# SCH_Water-Gauge_2025-03-27.net
KiCad netlist of a schematic drawn in EasyEDA
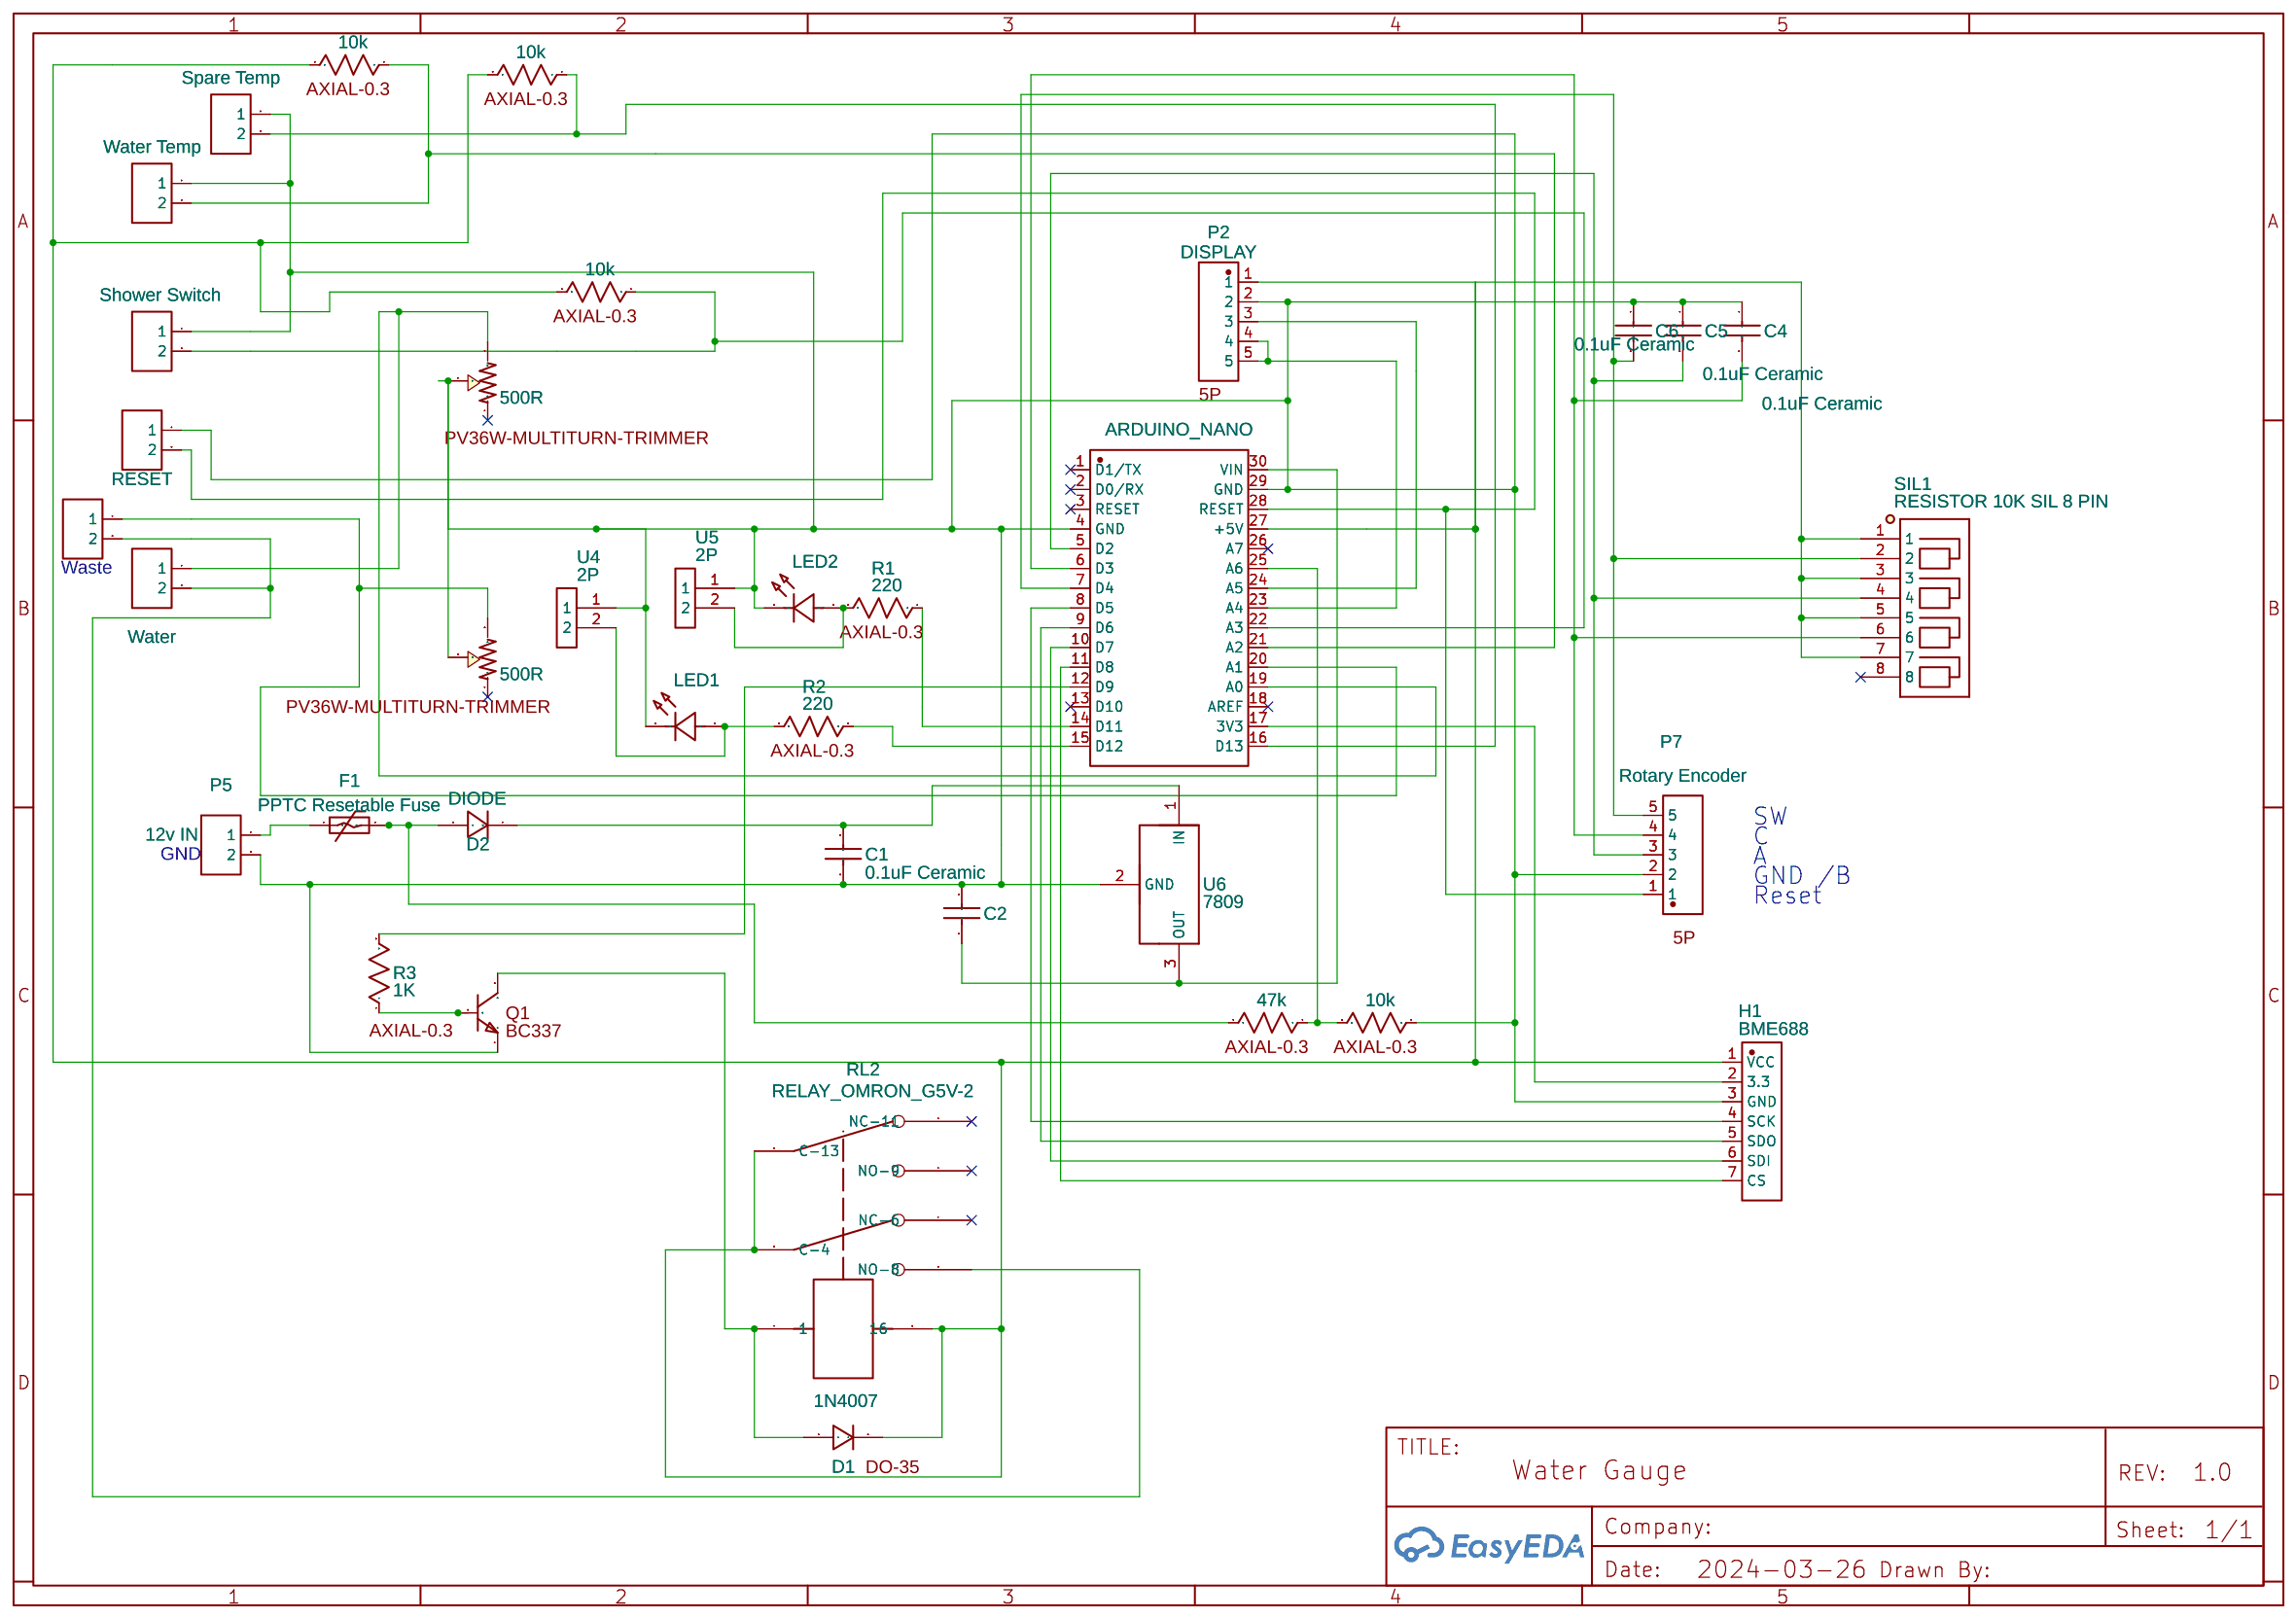
[diagram p0: schematic sheet]

(export (version "E")
  (design (tool "Eeschema 10.0.6"))
  (components
    (comp (ref "C1")
      (value "0.1uF Ceramic")
      (fields (field (name "Manufacturer Part") "Capacitor_Ceramic"))
      (libsource (lib "") (part "Capacitor_Ceramic"))
    )
    (comp (ref "C2")
      (value "0.1uF Ceramic")
      (fields (field (name "Manufacturer Part") "Capacitor_Ceramic"))
      (libsource (lib "") (part "Capacitor_Ceramic"))
    )
    (comp (ref "C4")
      (value "0.1uF Ceramic")
      (fields (field (name "Manufacturer Part") "Capacitor_Ceramic"))
      (libsource (lib "") (part "Capacitor_Ceramic"))
    )
    (comp (ref "C5")
      (value "0.1uF Ceramic")
      (fields (field (name "Manufacturer Part") "Capacitor_Ceramic"))
      (libsource (lib "") (part "Capacitor_Ceramic"))
    )
    (comp (ref "C6")
      (value "0.1uF Ceramic")
      (fields (field (name "Manufacturer Part") "Capacitor_Ceramic"))
      (libsource (lib "") (part "Capacitor_Ceramic"))
    )
    (comp (ref "D1") (value "1N4007") (libsource (lib "") (part "1N4007")))
    (comp (ref "D2")
      (value "DIODE")
      (fields (field (name "Manufacturer Part") "1N4007GR") (field (name "Manufacturer") "PINGWEI(平伟)"))
      (libsource (lib "") (part "1N4007GR"))
    )
    (comp (ref "F1")
      (value "PPTC Resetable Fuse")
      (fields (field (name "Manufacturer Part") "MF-R005-AP") (field (name "Manufacturer") "Bourns"))
      (libsource (lib "") (part "PPTC Resetable Fuse"))
    )
    (comp (ref "H1")
      (value "BME688")
      (fields (field (name "Manufacturer Part") "A2541WV-7P") (field (name "Manufacturer") "CJT(长江连接器)"))
      (libsource (lib "") (part "A2541WV-7P"))
    )
    (comp (ref "LED1")
      (value "LED2")
      (fields (field (name "Manufacturer Part") "15400394A3590") (field (name "Manufacturer") "Wurth(伍尔特)"))
      (libsource (lib "") (part "15400394A3590"))
    )
    (comp (ref "LED2")
      (value "LED1")
      (fields (field (name "Manufacturer Part") "15400394A3590") (field (name "Manufacturer") "Wurth(伍尔特)"))
      (libsource (lib "") (part "15400394A3590"))
    )
    (comp (ref "P1") (value "Water") (libsource (lib "") (part "CONN-TH_2P-P5.00_1")))
    (comp (ref "P2") (value "DISPLAY") (libsource (lib "") (part "5P_1")))
    (comp (ref "P3") (value "12v IN") (libsource (lib "") (part "CONN-TH_2P-P5.00_1")))
    (comp (ref "P4") (value "Shower Switch") (libsource (lib "") (part "CONN-TH_2P-P5.00_1")))
    (comp (ref "P5") (value "12v IN") (libsource (lib "") (part "CONN-TH_2P-P5.00_1")))
    (comp (ref "P6") (value "Water Temp") (libsource (lib "") (part "CONN-TH_2P-P5.00_1")))
    (comp (ref "P7") (value "Rotary Encoder") (libsource (lib "") (part "5P")))
    (comp (ref "P8") (value "Spare Temp") (libsource (lib "") (part "CONN-TH_2P-P5.00_1")))
    (comp (ref "Q1") (value "BD139") (libsource (lib "") (part "BC547")))
    (comp (ref "R1") (value "220") (libsource (lib "") (part "Resistor1")))
    (comp (ref "R2") (value "220") (libsource (lib "") (part "Resistor1")))
    (comp (ref "R3") (value "1K") (libsource (lib "") (part "Resistor1_1")))
    (comp (ref "R4") (value "47k") (libsource (lib "") (part "Resistor1")))
    (comp (ref "R5") (value "10k") (libsource (lib "") (part "Resistor1")))
    (comp (ref "R6") (value "10k") (libsource (lib "") (part "Resistor1")))
    (comp (ref "R9") (value "10k") (libsource (lib "") (part "Resistor1")))
    (comp (ref "R10") (value "10k") (libsource (lib "") (part "Resistor1")))
    (comp (ref "RESET") (value "12v IN") (libsource (lib "") (part "CONN-TH_2P-P5.00")))
    (comp (ref "RL2")
      (value "RELAY_OMRON_G5V-2")
      (fields (field (name "Manufacturer Part") "G5V-2") (field (name "Manufacturer") "Omron"))
      (libsource (lib "") (part "RELAY_OMRON_G5V-2"))
    )
    (comp (ref "SIL1") (value "RESISTOR 10K SIL 8 PIN") (libsource (lib "") (part "RESISTOR 10K SIL 8 PIN")))
    (comp (ref "U1") (value "ARDUINO_NANO") (libsource (lib "") (part "ARDUINO_NANO")))
    (comp (ref "U4") (value "2P") (libsource (lib "") (part "2P")))
    (comp (ref "U5") (value "2P") (libsource (lib "") (part "2P")))
    (comp (ref "U6")
      (value "7809")
      (fields (field (name "Manufacturer") "MOUSER"))
      (libsource (lib "") (part "7805"))
    )
    (comp (ref "WASTE")
      (value "500R")
      (fields (field (name "Manufacturer Part") "PV36W102C01B00") (field (name "Manufacturer") "Bourns"))
      (libsource (lib "") (part "1k_1"))
    )
    (comp (ref "WATER")
      (value "500R")
      (fields (field (name "Manufacturer Part") "PV36W102C01B00") (field (name "Manufacturer") "Bourns"))
      (libsource (lib "") (part "1k"))
    )
  )
  (nets
    (net (code "1") (name "Net-(D1-A)") (class "Default")
      (node (ref "D1") (pin "1") (pinfunction "A_1") (pintype "unspecified"))
      (node (ref "Q1") (pin "3") (pinfunction "C_3") (pintype "unspecified"))
      (node (ref "RL2") (pin "4") (pinfunction "1_4") (pintype "unspecified"))
    )
    (net (code "2") (name "Net-(D1-K)") (class "Default")
      (node (ref "D1") (pin "2") (pinfunction "K_2") (pintype "unspecified"))
      (node (ref "H1") (pin "1") (pinfunction "VCC_1") (pintype "unspecified"))
      (node (ref "P2") (pin "1") (pinfunction "1_1") (pintype "unspecified"))
      (node (ref "R10") (pin "2") (pinfunction "2_2") (pintype "unspecified"))
      (node (ref "R6") (pin "2") (pinfunction "2_2") (pintype "unspecified"))
      (node (ref "R9") (pin "2") (pinfunction "2_2") (pintype "unspecified"))
      (node (ref "RL2") (pin "3") (pinfunction "C-13_3") (pintype "unspecified"))
      (node (ref "RL2") (pin "5") (pinfunction "16_5") (pintype "unspecified"))
      (node (ref "RL2") (pin "6") (pinfunction "C-4_6") (pintype "unspecified"))
      (node (ref "SIL1") (pin "1") (pinfunction "1_1") (pintype "unspecified"))
      (node (ref "SIL1") (pin "3") (pinfunction "3_3") (pintype "unspecified"))
      (node (ref "SIL1") (pin "5") (pinfunction "5_5") (pintype "unspecified"))
      (node (ref "SIL1") (pin "7") (pinfunction "7_7") (pintype "unspecified"))
      (node (ref "U1") (pin "27") (pinfunction "+5V_27") (pintype "unspecified"))
    )
    (net (code "3") (name "Net-(D2-A)") (class "Default")
      (node (ref "D2") (pin "2") (pinfunction "A_2") (pintype "unspecified"))
      (node (ref "F1") (pin "2") (pinfunction "2_2") (pintype "unspecified"))
      (node (ref "R4") (pin "2") (pinfunction "2_2") (pintype "unspecified"))
    )
    (net (code "4") (name "Net-(D2-C)") (class "Default")
      (node (ref "C1") (pin "1") (pinfunction "1_1") (pintype "unspecified"))
      (node (ref "D2") (pin "1") (pinfunction "C_1") (pintype "unspecified"))
      (node (ref "U6") (pin "1") (pinfunction "IN_1") (pintype "unspecified"))
    )
    (net (code "5") (name "Net-(F1-Pad1)") (class "Default")
      (node (ref "F1") (pin "1") (pinfunction "1_1") (pintype "unspecified"))
      (node (ref "P5") (pin "1") (pinfunction "1_1") (pintype "unspecified"))
    )
    (net (code "6") (name "Net-(H1-3.3)") (class "Default")
      (node (ref "H1") (pin "2") (pinfunction "3.3_2") (pintype "unspecified"))
      (node (ref "U1") (pin "17") (pinfunction "3V3_17") (pintype "unspecified"))
    )
    (net (code "7") (name "Net-(H1-CS)") (class "Default")
      (node (ref "H1") (pin "7") (pinfunction "CS_7") (pintype "unspecified"))
      (node (ref "U1") (pin "11") (pinfunction "D8_11") (pintype "unspecified"))
    )
    (net (code "8") (name "Net-(H1-GND)") (class "Default")
      (node (ref "C1") (pin "2") (pinfunction "2_2") (pintype "unspecified"))
      (node (ref "C2") (pin "1") (pinfunction "1_1") (pintype "unspecified"))
      (node (ref "C4") (pin "1") (pinfunction "1_1") (pintype "unspecified"))
      (node (ref "C5") (pin "1") (pinfunction "1_1") (pintype "unspecified"))
      (node (ref "C6") (pin "1") (pinfunction "1_1") (pintype "unspecified"))
      (node (ref "H1") (pin "3") (pinfunction "GND_3") (pintype "unspecified"))
      (node (ref "LED1") (pin "1") (pinfunction "K_1") (pintype "unspecified"))
      (node (ref "LED2") (pin "1") (pinfunction "K_1") (pintype "unspecified"))
      (node (ref "P1") (pin "1") (pinfunction "1_1") (pintype "unspecified"))
      (node (ref "P2") (pin "2") (pinfunction "2_2") (pintype "unspecified"))
      (node (ref "P4") (pin "1") (pinfunction "1_1") (pintype "unspecified"))
      (node (ref "P5") (pin "2") (pinfunction "2_2") (pintype "unspecified"))
      (node (ref "P6") (pin "1") (pinfunction "1_1") (pintype "unspecified"))
      (node (ref "P7") (pin "2") (pinfunction "2_2") (pintype "unspecified"))
      (node (ref "P8") (pin "1") (pinfunction "1_1") (pintype "unspecified"))
      (node (ref "Q1") (pin "1") (pinfunction "E_1") (pintype "unspecified"))
      (node (ref "R5") (pin "1") (pinfunction "1_1") (pintype "unspecified"))
      (node (ref "U1") (pin "29") (pinfunction "GND_29") (pintype "unspecified"))
      (node (ref "U1") (pin "4") (pinfunction "GND_4") (pintype "unspecified"))
      (node (ref "U4") (pin "1") (pinfunction "1_1") (pintype "unspecified"))
      (node (ref "U5") (pin "1") (pinfunction "1_1") (pintype "unspecified"))
      (node (ref "U6") (pin "2") (pinfunction "GND_2") (pintype "unspecified"))
      (node (ref "WASTE") (pin "2") (pinfunction "2_2") (pintype "unspecified"))
      (node (ref "WATER") (pin "2") (pinfunction "2_2") (pintype "unspecified"))
    )
    (net (code "9") (name "Net-(H1-SCK)") (class "Default")
      (node (ref "H1") (pin "4") (pinfunction "SCK_4") (pintype "unspecified"))
      (node (ref "U1") (pin "8") (pinfunction "D5_8") (pintype "unspecified"))
    )
    (net (code "10") (name "Net-(H1-SDI)") (class "Default")
      (node (ref "H1") (pin "6") (pinfunction "SDI_6") (pintype "unspecified"))
      (node (ref "U1") (pin "10") (pinfunction "D7_10") (pintype "unspecified"))
    )
    (net (code "11") (name "Net-(H1-SDO)") (class "Default")
      (node (ref "H1") (pin "5") (pinfunction "SDO_5") (pintype "unspecified"))
      (node (ref "U1") (pin "9") (pinfunction "D6_9") (pintype "unspecified"))
    )
    (net (code "12") (name "Net-(LED1-A)") (class "Default")
      (node (ref "LED1") (pin "2") (pinfunction "A_2") (pintype "unspecified"))
      (node (ref "R1") (pin "2") (pinfunction "2_2") (pintype "unspecified"))
      (node (ref "U5") (pin "2") (pinfunction "2_2") (pintype "unspecified"))
    )
    (net (code "13") (name "Net-(LED2-A)") (class "Default")
      (node (ref "LED2") (pin "2") (pinfunction "A_2") (pintype "unspecified"))
      (node (ref "R2") (pin "2") (pinfunction "2_2") (pintype "unspecified"))
      (node (ref "U4") (pin "2") (pinfunction "2_2") (pintype "unspecified"))
    )
    (net (code "14") (name "Net-(P1-Pad2)") (class "Default")
      (node (ref "P1") (pin "2") (pinfunction "2_2") (pintype "unspecified"))
      (node (ref "P7") (pin "1") (pinfunction "1_1") (pintype "unspecified"))
      (node (ref "U1") (pin "28") (pinfunction "RESET_28") (pintype "unspecified"))
    )
    (net (code "15") (name "Net-(Q1-B)") (class "Default")
      (node (ref "Q1") (pin "2") (pinfunction "B_2") (pintype "unspecified"))
      (node (ref "R3") (pin "1") (pinfunction "1_1") (pintype "unspecified"))
    )
    (net (code "16") (name "Net-(RL2-NO-8)") (class "Default")
      (node (ref "P3") (pin "2") (pinfunction "2_2") (pintype "unspecified"))
      (node (ref "RESET") (pin "2") (pinfunction "2_2") (pintype "unspecified"))
      (node (ref "RL2") (pin "8") (pinfunction "NO-8_8") (pintype "unspecified"))
    )
    (net (code "17") (name "Net-(U1-A0)") (class "Default")
      (node (ref "RESET") (pin "1") (pinfunction "1_1") (pintype "unspecified"))
      (node (ref "U1") (pin "19") (pinfunction "A0_19") (pintype "unspecified"))
      (node (ref "WATER") (pin "3") (pinfunction "3_3") (pintype "unspecified"))
    )
    (net (code "18") (name "Net-(U1-A1)") (class "Default")
      (node (ref "P3") (pin "1") (pinfunction "1_1") (pintype "unspecified"))
      (node (ref "U1") (pin "20") (pinfunction "A1_20") (pintype "unspecified"))
      (node (ref "WASTE") (pin "3") (pinfunction "3_3") (pintype "unspecified"))
    )
    (net (code "19") (name "Net-(U1-A2)") (class "Default")
      (node (ref "P6") (pin "2") (pinfunction "2_2") (pintype "unspecified"))
      (node (ref "R9") (pin "1") (pinfunction "1_1") (pintype "unspecified"))
      (node (ref "U1") (pin "21") (pinfunction "A2_21") (pintype "unspecified"))
    )
    (net (code "20") (name "Net-(U1-A3)") (class "Default")
      (node (ref "P4") (pin "2") (pinfunction "2_2") (pintype "unspecified"))
      (node (ref "R10") (pin "1") (pinfunction "1_1") (pintype "unspecified"))
      (node (ref "U1") (pin "22") (pinfunction "A3_22") (pintype "unspecified"))
    )
    (net (code "21") (name "Net-(U1-A4)") (class "Default")
      (node (ref "P2") (pin "4") (pinfunction "4_4") (pintype "unspecified"))
      (node (ref "P2") (pin "5") (pinfunction "5_5") (pintype "unspecified"))
      (node (ref "U1") (pin "23") (pinfunction "A4_23") (pintype "unspecified"))
    )
    (net (code "22") (name "Net-(U1-A5)") (class "Default")
      (node (ref "P2") (pin "3") (pinfunction "3_3") (pintype "unspecified"))
      (node (ref "U1") (pin "24") (pinfunction "A5_24") (pintype "unspecified"))
    )
    (net (code "23") (name "Net-(U1-A6)") (class "Default")
      (node (ref "R4") (pin "1") (pinfunction "1_1") (pintype "unspecified"))
      (node (ref "R5") (pin "2") (pinfunction "2_2") (pintype "unspecified"))
      (node (ref "U1") (pin "25") (pinfunction "A6_25") (pintype "unspecified"))
    )
    (net (code "24") (name "Net-(U1-D2)") (class "Default")
      (node (ref "C5") (pin "2") (pinfunction "2_2") (pintype "unspecified"))
      (node (ref "P7") (pin "3") (pinfunction "3_3") (pintype "unspecified"))
      (node (ref "SIL1") (pin "4") (pinfunction "4_4") (pintype "unspecified"))
      (node (ref "U1") (pin "5") (pinfunction "D2_5") (pintype "unspecified"))
    )
    (net (code "25") (name "Net-(U1-D3)") (class "Default")
      (node (ref "C4") (pin "2") (pinfunction "2_2") (pintype "unspecified"))
      (node (ref "P7") (pin "4") (pinfunction "4_4") (pintype "unspecified"))
      (node (ref "SIL1") (pin "6") (pinfunction "6_6") (pintype "unspecified"))
      (node (ref "U1") (pin "6") (pinfunction "D3_6") (pintype "unspecified"))
    )
    (net (code "26") (name "Net-(U1-D4)") (class "Default")
      (node (ref "C6") (pin "2") (pinfunction "2_2") (pintype "unspecified"))
      (node (ref "P7") (pin "5") (pinfunction "5_5") (pintype "unspecified"))
      (node (ref "SIL1") (pin "2") (pinfunction "2_2") (pintype "unspecified"))
      (node (ref "U1") (pin "7") (pinfunction "D4_7") (pintype "unspecified"))
    )
    (net (code "27") (name "Net-(U1-D9)") (class "Default")
      (node (ref "R3") (pin "2") (pinfunction "2_2") (pintype "unspecified"))
      (node (ref "U1") (pin "12") (pinfunction "D9_12") (pintype "unspecified"))
    )
    (net (code "28") (name "Net-(U1-D11)") (class "Default")
      (node (ref "R1") (pin "1") (pinfunction "1_1") (pintype "unspecified"))
      (node (ref "U1") (pin "14") (pinfunction "D11_14") (pintype "unspecified"))
    )
    (net (code "29") (name "Net-(U1-D12)") (class "Default")
      (node (ref "R2") (pin "1") (pinfunction "1_1") (pintype "unspecified"))
      (node (ref "U1") (pin "15") (pinfunction "D12_15") (pintype "unspecified"))
    )
    (net (code "30") (name "Net-(U1-D13)") (class "Default")
      (node (ref "P8") (pin "2") (pinfunction "2_2") (pintype "unspecified"))
      (node (ref "R6") (pin "1") (pinfunction "1_1") (pintype "unspecified"))
      (node (ref "U1") (pin "16") (pinfunction "D13_16") (pintype "unspecified"))
    )
    (net (code "31") (name "Net-(U1-VIN)") (class "Default")
      (node (ref "C2") (pin "2") (pinfunction "2_2") (pintype "unspecified"))
      (node (ref "U1") (pin "30") (pinfunction "VIN_30") (pintype "unspecified"))
      (node (ref "U6") (pin "3") (pinfunction "OUT_3") (pintype "unspecified"))
    )
    (net (code "32") (name "unconnected-(RL2-NC-6-Pad7)") (class "Default")
      (node (ref "RL2") (pin "7") (pinfunction "NC-6_7") (pintype "unspecified+no_connect"))
    )
    (net (code "33") (name "unconnected-(RL2-NC-11-Pad2)") (class "Default")
      (node (ref "RL2") (pin "2") (pinfunction "NC-11_2") (pintype "unspecified+no_connect"))
    )
    (net (code "34") (name "unconnected-(RL2-NO-9-Pad1)") (class "Default")
      (node (ref "RL2") (pin "1") (pinfunction "NO-9_1") (pintype "unspecified+no_connect"))
    )
    (net (code "35") (name "unconnected-(SIL1-Pad8)") (class "Default")
      (node (ref "SIL1") (pin "8") (pinfunction "8_8") (pintype "unspecified+no_connect"))
    )
    (net (code "36") (name "unconnected-(U1-A7-Pad26)") (class "Default")
      (node (ref "U1") (pin "26") (pinfunction "A7_26") (pintype "unspecified+no_connect"))
    )
    (net (code "37") (name "unconnected-(U1-AREF-Pad18)") (class "Default")
      (node (ref "U1") (pin "18") (pinfunction "AREF_18") (pintype "unspecified+no_connect"))
    )
    (net (code "38") (name "unconnected-(U1-D0{slash}RX-Pad2)") (class "Default")
      (node (ref "U1") (pin "2") (pinfunction "D0/RX_2") (pintype "unspecified+no_connect"))
    )
    (net (code "39") (name "unconnected-(U1-D1{slash}TX-Pad1)") (class "Default")
      (node (ref "U1") (pin "1") (pinfunction "D1/TX_1") (pintype "unspecified+no_connect"))
    )
    (net (code "40") (name "unconnected-(U1-D10-Pad13)") (class "Default")
      (node (ref "U1") (pin "13") (pinfunction "D10_13") (pintype "unspecified+no_connect"))
    )
    (net (code "41") (name "unconnected-(U1-RESET-Pad3)") (class "Default")
      (node (ref "U1") (pin "3") (pinfunction "RESET_3") (pintype "unspecified+no_connect"))
    )
    (net (code "42") (name "unconnected-(WASTE-Pad1)") (class "Default")
      (node (ref "WASTE") (pin "1") (pinfunction "1_1") (pintype "unspecified+no_connect"))
    )
    (net (code "43") (name "unconnected-(WATER-Pad1)") (class "Default")
      (node (ref "WATER") (pin "1") (pinfunction "1_1") (pintype "unspecified+no_connect"))
    )
  )
)
